# microSD-v2017-2.net
KiCad netlist of a schematic drawn in EAGLE
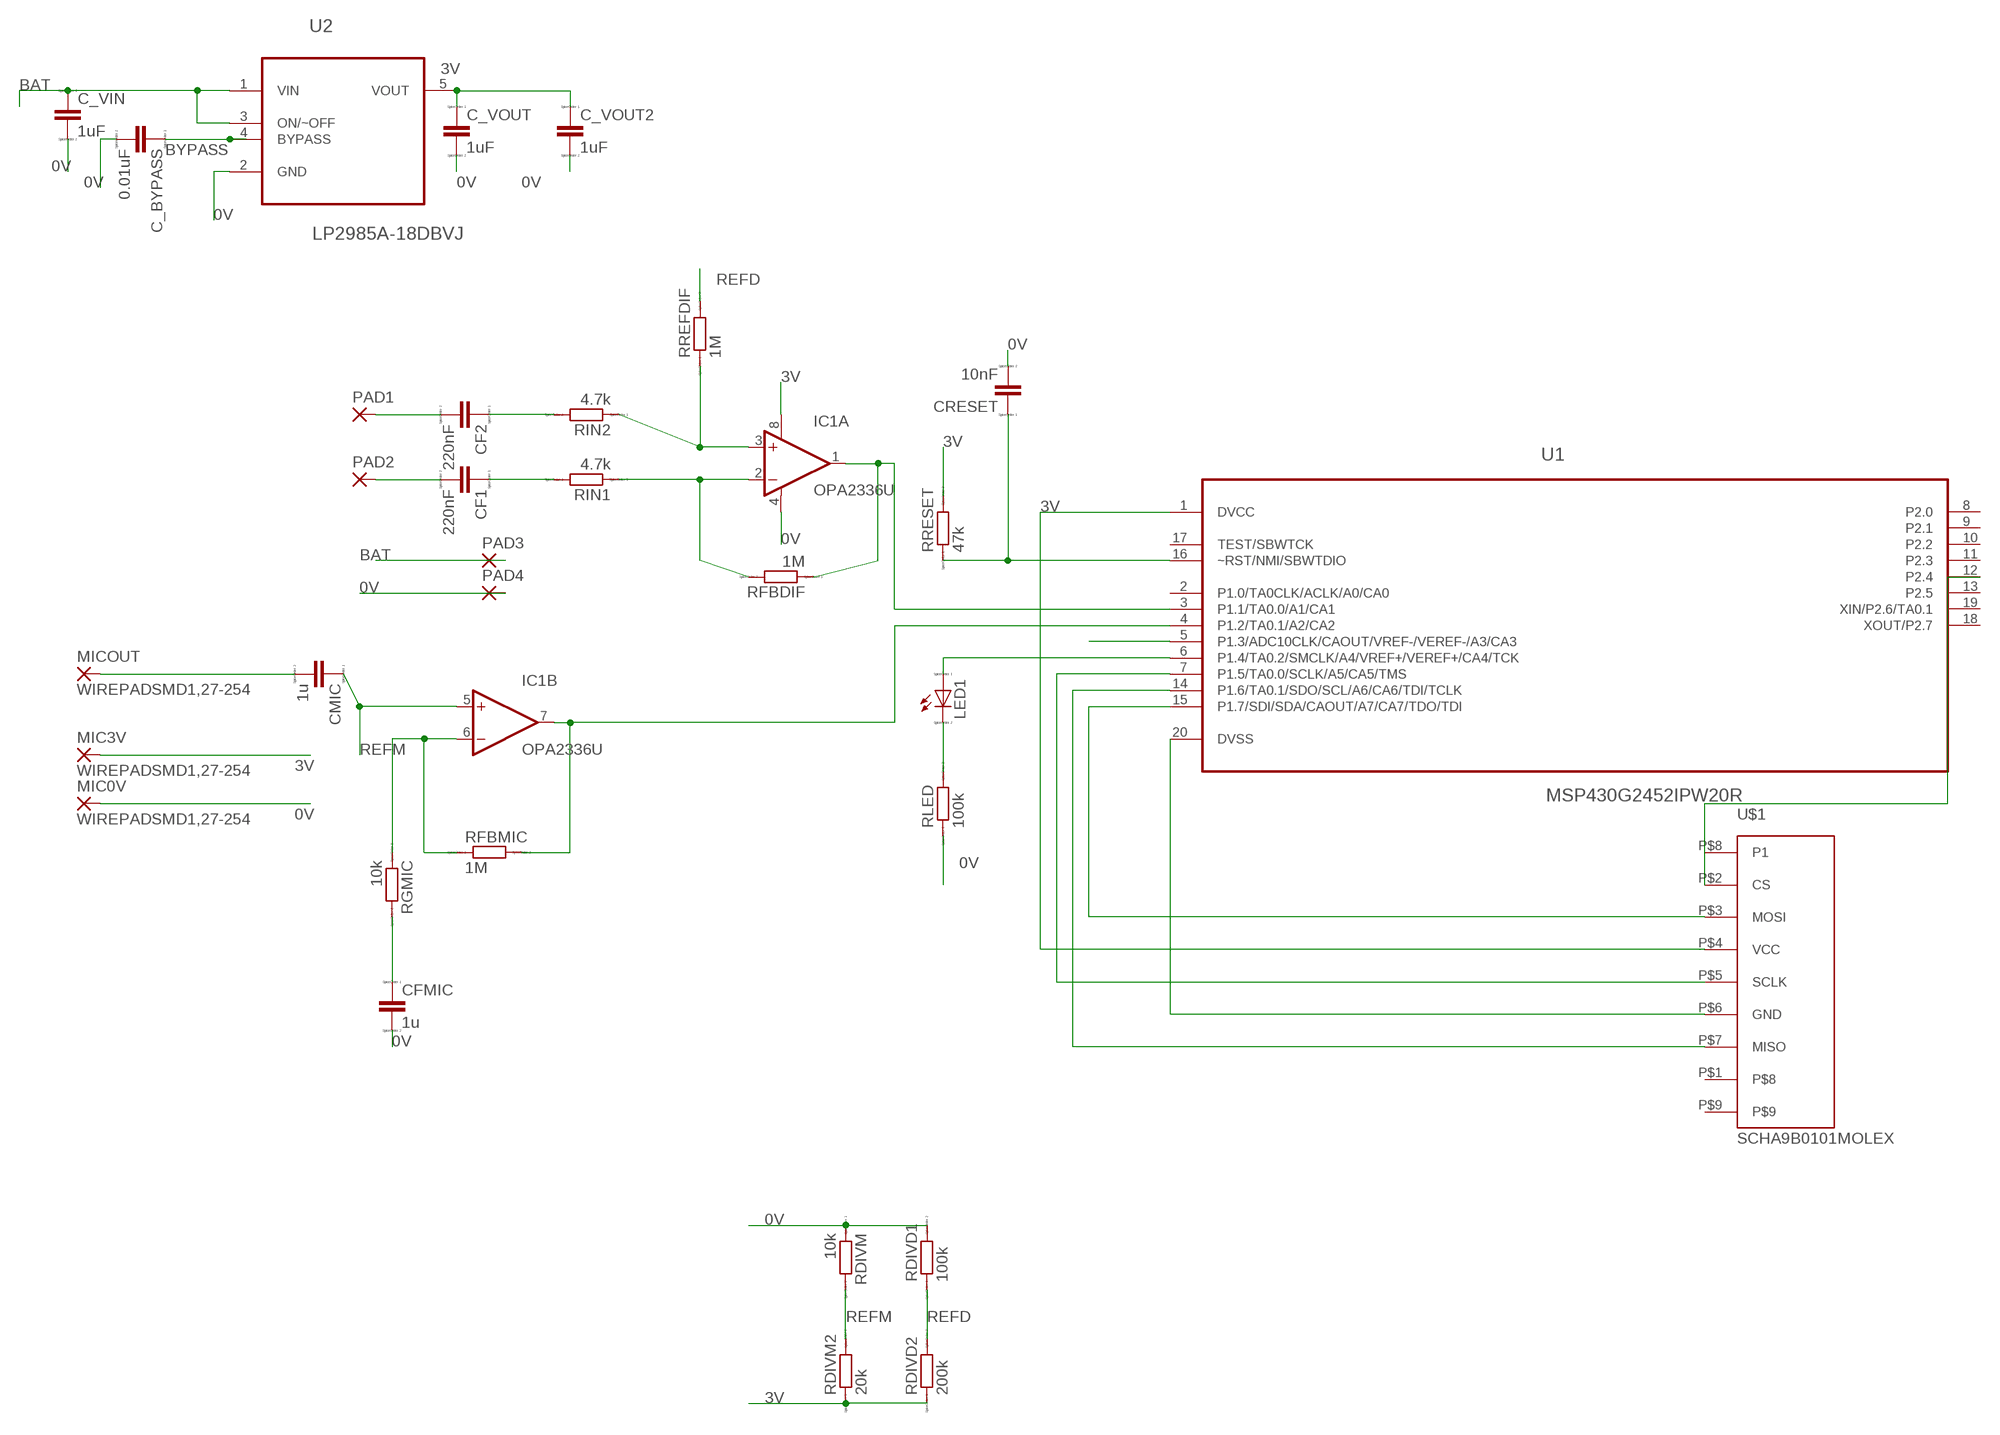
[diagram p0: schematic, sheet 1]

(export (version "E")
  (design (tool "Eeschema 10.0.6"))
  (components
    (comp (ref "CF1")
      (value "220nF")
      (footprint "eagle-import:C0805")
      (libsource (lib "eagle-import") (part "C"))
    )
    (comp (ref "CF2")
      (value "220nF")
      (footprint "eagle-import:C0805")
      (libsource (lib "eagle-import") (part "C"))
    )
    (comp (ref "CFMIC")
      (value "1u")
      (footprint "eagle-import:C0805")
      (libsource (lib "eagle-import") (part "C"))
    )
    (comp (ref "CMIC")
      (value "1u")
      (footprint "eagle-import:C0805")
      (libsource (lib "eagle-import") (part "C"))
    )
    (comp (ref "CRESET")
      (value "10nF")
      (footprint "eagle-import:C0805")
      (libsource (lib "eagle-import") (part "C"))
    )
    (comp (ref "C_BYPASS")
      (value "0.01uF")
      (footprint "eagle-import:C0805")
      (libsource (lib "eagle-import") (part "C"))
    )
    (comp (ref "C_VIN")
      (value "1uF")
      (footprint "eagle-import:C0805")
      (libsource (lib "eagle-import") (part "C"))
    )
    (comp (ref "C_VOUT")
      (value "1uF")
      (footprint "eagle-import:C0805")
      (libsource (lib "eagle-import") (part "C"))
    )
    (comp (ref "C_VOUT2")
      (value "1uF")
      (footprint "eagle-import:C0805")
      (libsource (lib "eagle-import") (part "C"))
    )
    (comp (ref "IC1")
      (value "OPA2336U")
      (footprint "eagle-import:SO08")
      (fields (field (name "MPN") "OPA2336UA"))
      (libsource (lib "eagle-import") (part "OPA2336U"))
    )
    (comp (ref "LED1")
      (value "LED_ESML0603")
      (footprint "eagle-import:LED_SML0603")
      (libsource (lib "eagle-import") (part "LED_ESML0603"))
    )
    (comp (ref "MIC0V")
      (value "WIREPADSMD1,27-254")
      (footprint "eagle-import:SMD1,27-2,54")
      (libsource (lib "eagle-import") (part "WIREPADSMD1,27-254"))
    )
    (comp (ref "MIC3V")
      (value "WIREPADSMD1,27-254")
      (footprint "eagle-import:SMD1,27-2,54")
      (libsource (lib "eagle-import") (part "WIREPADSMD1,27-254"))
    )
    (comp (ref "MICOUT")
      (value "WIREPADSMD1,27-254")
      (footprint "eagle-import:SMD1,27-2,54")
      (libsource (lib "eagle-import") (part "WIREPADSMD1,27-254"))
    )
    (comp (ref "PAD1")
      (value "SMD2")
      (footprint "eagle-import:SMD1,27-2,54")
      (libsource (lib "eagle-import") (part "SMD2"))
    )
    (comp (ref "PAD2")
      (value "SMD2")
      (footprint "eagle-import:SMD1,27-2,54")
      (libsource (lib "eagle-import") (part "SMD2"))
    )
    (comp (ref "PAD3")
      (value "SMD2")
      (footprint "eagle-import:SMD1,27-2,54")
      (libsource (lib "eagle-import") (part "SMD2"))
    )
    (comp (ref "PAD4")
      (value "SMD2")
      (footprint "eagle-import:SMD1,27-2,54")
      (libsource (lib "eagle-import") (part "SMD2"))
    )
    (comp (ref "RDIVD1")
      (value "100k")
      (footprint "eagle-import:R0805")
      (libsource (lib "eagle-import") (part "R"))
    )
    (comp (ref "RDIVD2")
      (value "200k")
      (footprint "eagle-import:R0805")
      (libsource (lib "eagle-import") (part "R"))
    )
    (comp (ref "RDIVM")
      (value "10k")
      (footprint "eagle-import:R0805")
      (libsource (lib "eagle-import") (part "R"))
    )
    (comp (ref "RDIVM2")
      (value "20k")
      (footprint "eagle-import:R0805")
      (libsource (lib "eagle-import") (part "R"))
    )
    (comp (ref "RFBDIF")
      (value "1M")
      (footprint "eagle-import:R0805")
      (libsource (lib "eagle-import") (part "R"))
    )
    (comp (ref "RFBMIC")
      (value "1M")
      (footprint "eagle-import:R0805")
      (libsource (lib "eagle-import") (part "R"))
    )
    (comp (ref "RGMIC")
      (value "10k")
      (footprint "eagle-import:R0805")
      (libsource (lib "eagle-import") (part "R"))
    )
    (comp (ref "RIN1")
      (value "4.7k")
      (footprint "eagle-import:R0805")
      (libsource (lib "eagle-import") (part "R"))
    )
    (comp (ref "RIN2")
      (value "4.7k")
      (footprint "eagle-import:R0805")
      (libsource (lib "eagle-import") (part "R"))
    )
    (comp (ref "RLED")
      (value "100k")
      (footprint "eagle-import:R0603")
      (libsource (lib "eagle-import") (part "RR0603"))
    )
    (comp (ref "RREFDIF")
      (value "1M")
      (footprint "eagle-import:R0805")
      (libsource (lib "eagle-import") (part "R"))
    )
    (comp (ref "RRESET")
      (value "47k")
      (footprint "eagle-import:R0805")
      (libsource (lib "eagle-import") (part "R"))
    )
    (comp (ref "U$1")
      (value "SCHA9B0101MOLEX")
      (footprint "eagle-import:SMD-MOLEX")
      (libsource (lib "eagle-import") (part "SCHA9B0101MOLEX"))
    )
    (comp (ref "U1")
      (value "MSP430G2452IPW20R")
      (footprint "eagle-import:SOP65P640X120-20N")
      (libsource (lib "eagle-import") (part "MSP430G2452IPW20R"))
    )
    (comp (ref "U2")
      (value "LP2985A-18DBVJ")
      (footprint "eagle-import:SOT95P280X145-5N")
      (libsource (lib "eagle-import") (part "LP2985A-18DBVJ"))
    )
  )
  (nets
    (net (code "1") (name "/0V") (class "Default")
      (node (ref "CFMIC") (pin "2") (pinfunction "2_2") (pintype "passive"))
      (node (ref "CRESET") (pin "2") (pinfunction "2_2") (pintype "passive"))
      (node (ref "C_BYPASS") (pin "2") (pinfunction "2_2") (pintype "passive"))
      (node (ref "C_VIN") (pin "2") (pinfunction "2_2") (pintype "passive"))
      (node (ref "C_VOUT") (pin "2") (pinfunction "2_2") (pintype "passive"))
      (node (ref "C_VOUT2") (pin "2") (pinfunction "2_2") (pintype "passive"))
      (node (ref "IC1") (pin "4") (pinfunction "V-_4") (pintype "power_in"))
      (node (ref "MIC0V") (pin "1") (pinfunction "P_1") (pintype "passive"))
      (node (ref "PAD4") (pin "1") (pinfunction "P_1") (pintype "passive"))
      (node (ref "RDIVD1") (pin "2") (pinfunction "2_2") (pintype "passive"))
      (node (ref "RDIVM") (pin "1") (pinfunction "1_1") (pintype "passive"))
      (node (ref "RLED") (pin "1") (pinfunction "1_1") (pintype "passive"))
      (node (ref "U$1") (pin "P$6") (pinfunction "GND_P$6") (pintype "bidirectional"))
      (node (ref "U1") (pin "20") (pinfunction "DVSS_20") (pintype "passive"))
      (node (ref "U2") (pin "2") (pinfunction "GND_2") (pintype "passive"))
    )
    (net (code "2") (name "/3V") (class "Default")
      (node (ref "C_VOUT") (pin "1") (pinfunction "1_1") (pintype "passive"))
      (node (ref "C_VOUT2") (pin "1") (pinfunction "1_1") (pintype "passive"))
      (node (ref "IC1") (pin "8") (pinfunction "V+_8") (pintype "power_in"))
      (node (ref "MIC3V") (pin "1") (pinfunction "P_1") (pintype "passive"))
      (node (ref "RDIVD2") (pin "1") (pinfunction "1_1") (pintype "passive"))
      (node (ref "RDIVM2") (pin "1") (pinfunction "1_1") (pintype "passive"))
      (node (ref "RRESET") (pin "2") (pinfunction "2_2") (pintype "passive"))
      (node (ref "U$1") (pin "P$4") (pinfunction "VCC_P$4") (pintype "bidirectional"))
      (node (ref "U1") (pin "1") (pinfunction "DVCC_1") (pintype "power_in"))
      (node (ref "U2") (pin "5") (pinfunction "VOUT_5") (pintype "output"))
    )
    (net (code "3") (name "/BAT") (class "Default")
      (node (ref "C_VIN") (pin "1") (pinfunction "1_1") (pintype "passive"))
      (node (ref "PAD3") (pin "1") (pinfunction "P_1") (pintype "passive"))
      (node (ref "U2") (pin "1") (pinfunction "VIN_1") (pintype "input"))
      (node (ref "U2") (pin "3") (pinfunction "ON/~{OFF}_3") (pintype "input"))
    )
    (net (code "4") (name "/BYPASS") (class "Default")
      (node (ref "C_BYPASS") (pin "1") (pinfunction "1_1") (pintype "passive"))
      (node (ref "U2") (pin "4") (pinfunction "BYPASS_4") (pintype "input"))
    )
    (net (code "5") (name "/REFD") (class "Default")
      (node (ref "RDIVD1") (pin "1") (pinfunction "1_1") (pintype "passive"))
      (node (ref "RDIVD2") (pin "2") (pinfunction "2_2") (pintype "passive"))
      (node (ref "RREFDIF") (pin "2") (pinfunction "2_2") (pintype "passive"))
    )
    (net (code "6") (name "/REFM") (class "Default")
      (node (ref "CMIC") (pin "1") (pinfunction "1_1") (pintype "passive"))
      (node (ref "IC1") (pin "5") (pinfunction "+IN_5") (pintype "input"))
      (node (ref "RDIVM") (pin "2") (pinfunction "2_2") (pintype "passive"))
      (node (ref "RDIVM2") (pin "2") (pinfunction "2_2") (pintype "passive"))
    )
    (net (code "7") (name "Net-(CF1-Pad1)") (class "Default")
      (node (ref "CF1") (pin "1") (pinfunction "1_1") (pintype "passive"))
      (node (ref "RIN1") (pin "2") (pinfunction "2_2") (pintype "passive"))
    )
    (net (code "8") (name "Net-(CF2-Pad1)") (class "Default")
      (node (ref "CF2") (pin "1") (pinfunction "1_1") (pintype "passive"))
      (node (ref "RIN2") (pin "2") (pinfunction "2_2") (pintype "passive"))
    )
    (net (code "9") (name "Net-(CFMIC-Pad1)") (class "Default")
      (node (ref "CFMIC") (pin "1") (pinfunction "1_1") (pintype "passive"))
      (node (ref "RGMIC") (pin "2") (pinfunction "2_2") (pintype "passive"))
    )
    (net (code "10") (name "Net-(IC1A-+IN)") (class "Default")
      (node (ref "IC1") (pin "3") (pinfunction "+IN_3") (pintype "input"))
      (node (ref "RIN2") (pin "1") (pinfunction "1_1") (pintype "passive"))
      (node (ref "RREFDIF") (pin "1") (pinfunction "1_1") (pintype "passive"))
    )
    (net (code "11") (name "Net-(IC1A--IN)") (class "Default")
      (node (ref "IC1") (pin "2") (pinfunction "-IN_2") (pintype "input"))
      (node (ref "RFBDIF") (pin "2") (pinfunction "2_2") (pintype "passive"))
      (node (ref "RIN1") (pin "1") (pinfunction "1_1") (pintype "passive"))
    )
    (net (code "12") (name "Net-(IC1A-OUT)") (class "Default")
      (node (ref "IC1") (pin "1") (pinfunction "OUT_1") (pintype "output"))
      (node (ref "RFBDIF") (pin "1") (pinfunction "1_1") (pintype "passive"))
      (node (ref "U1") (pin "3") (pinfunction "P1.1/TA0.0/A1/CA1_3") (pintype "bidirectional"))
    )
    (net (code "13") (name "Net-(IC1B--IN)") (class "Default")
      (node (ref "IC1") (pin "6") (pinfunction "-IN_6") (pintype "input"))
      (node (ref "RFBMIC") (pin "1") (pinfunction "1_1") (pintype "passive"))
      (node (ref "RGMIC") (pin "1") (pinfunction "1_1") (pintype "passive"))
    )
    (net (code "14") (name "Net-(IC1B-OUT)") (class "Default")
      (node (ref "IC1") (pin "7") (pinfunction "OUT_7") (pintype "output"))
      (node (ref "RFBMIC") (pin "2") (pinfunction "2_2") (pintype "passive"))
      (node (ref "U1") (pin "4") (pinfunction "P1.2/TA0.1/A2/CA2_4") (pintype "bidirectional"))
    )
    (net (code "15") (name "Net-(LED1-PadC)") (class "Default")
      (node (ref "LED1") (pin "C") (pinfunction "C_C") (pintype "passive"))
      (node (ref "RLED") (pin "2") (pinfunction "2_2") (pintype "passive"))
    )
    (net (code "16") (name "Net-(MICOUT-P)") (class "Default")
      (node (ref "CMIC") (pin "2") (pinfunction "2_2") (pintype "passive"))
      (node (ref "MICOUT") (pin "1") (pinfunction "P_1") (pintype "passive"))
    )
    (net (code "17") (name "Net-(PAD1-P)") (class "Default")
      (node (ref "CF2") (pin "2") (pinfunction "2_2") (pintype "passive"))
      (node (ref "PAD1") (pin "1") (pinfunction "P_1") (pintype "passive"))
    )
    (net (code "18") (name "Net-(PAD2-P)") (class "Default")
      (node (ref "CF1") (pin "2") (pinfunction "2_2") (pintype "passive"))
      (node (ref "PAD2") (pin "1") (pinfunction "P_1") (pintype "passive"))
    )
    (net (code "19") (name "Net-(U$1-CS)") (class "Default")
      (node (ref "U$1") (pin "P$2") (pinfunction "CS_P$2") (pintype "bidirectional"))
      (node (ref "U1") (pin "12") (pinfunction "P2.4_12") (pintype "bidirectional"))
    )
    (net (code "20") (name "Net-(U$1-MISO)") (class "Default")
      (node (ref "U$1") (pin "P$7") (pinfunction "MISO_P$7") (pintype "bidirectional"))
      (node (ref "U1") (pin "14") (pinfunction "P1.6/TA0.1/SDO/SCL/A6/CA6/TDI/TCLK_14") (pintype "bidirectional"))
    )
    (net (code "21") (name "Net-(U$1-MOSI)") (class "Default")
      (node (ref "U$1") (pin "P$3") (pinfunction "MOSI_P$3") (pintype "bidirectional"))
      (node (ref "U1") (pin "15") (pinfunction "P1.7/SDI/SDA/CAOUT/A7/CA7/TDO/TDI_15") (pintype "bidirectional"))
    )
    (net (code "22") (name "Net-(U$1-SCLK)") (class "Default")
      (node (ref "U$1") (pin "P$5") (pinfunction "SCLK_P$5") (pintype "bidirectional"))
      (node (ref "U1") (pin "7") (pinfunction "P1.5/TA0.0/SCLK/A5/CA5/TMS_7") (pintype "bidirectional"))
    )
    (net (code "23") (name "Net-(U1-P1.4{slash}TA0.2{slash}SMCLK{slash}A4{slash}VREF+{slash}VEREF+{slash}CA4{slash}TCK)") (class "Default")
      (node (ref "LED1") (pin "A") (pinfunction "A_A") (pintype "passive"))
      (node (ref "U1") (pin "6") (pinfunction "P1.4/TA0.2/SMCLK/A4/VREF+/VEREF+/CA4/TCK_6") (pintype "bidirectional"))
    )
    (net (code "24") (name "Net-(U1-~{RST{slash}NMI{slash}SBWTDIO})") (class "Default")
      (node (ref "CRESET") (pin "1") (pinfunction "1_1") (pintype "passive"))
      (node (ref "RRESET") (pin "1") (pinfunction "1_1") (pintype "passive"))
      (node (ref "U1") (pin "16") (pinfunction "~{RST/NMI/SBWTDIO}_16") (pintype "input"))
    )
    (net (code "25") (name "unconnected-(U$1-P$8-PadP$1)") (class "Default")
      (node (ref "U$1") (pin "P$1") (pinfunction "P$8_P$1") (pintype "bidirectional"))
    )
    (net (code "26") (name "unconnected-(U$1-P1-PadP$8)") (class "Default")
      (node (ref "U$1") (pin "P$8") (pinfunction "P1_P$8") (pintype "bidirectional"))
    )
    (net (code "27") (name "unconnected-(U$1-PadP$9)") (class "Default")
      (node (ref "U$1") (pin "P$9") (pinfunction "P$9_P$9") (pintype "bidirectional"))
    )
    (net (code "28") (name "unconnected-(U1-P1.0{slash}TA0CLK{slash}ACLK{slash}A0{slash}CA0-Pad2)") (class "Default")
      (node (ref "U1") (pin "2") (pinfunction "P1.0/TA0CLK/ACLK/A0/CA0_2") (pintype "bidirectional"))
    )
    (net (code "29") (name "unconnected-(U1-P1.3{slash}ADC10CLK{slash}CAOUT{slash}VREF-{slash}VEREF-{slash}A3{slash}CA3-Pad5)") (class "Default")
      (node (ref "U1") (pin "5") (pinfunction "P1.3/ADC10CLK/CAOUT/VREF-/VEREF-/A3/CA3_5") (pintype "bidirectional"))
    )
    (net (code "30") (name "unconnected-(U1-P2.0-Pad8)") (class "Default")
      (node (ref "U1") (pin "8") (pinfunction "P2.0_8") (pintype "bidirectional"))
    )
    (net (code "31") (name "unconnected-(U1-P2.1-Pad9)") (class "Default")
      (node (ref "U1") (pin "9") (pinfunction "P2.1_9") (pintype "bidirectional"))
    )
    (net (code "32") (name "unconnected-(U1-P2.2-Pad10)") (class "Default")
      (node (ref "U1") (pin "10") (pinfunction "P2.2_10") (pintype "bidirectional"))
    )
    (net (code "33") (name "unconnected-(U1-P2.3-Pad11)") (class "Default")
      (node (ref "U1") (pin "11") (pinfunction "P2.3_11") (pintype "bidirectional"))
    )
    (net (code "34") (name "unconnected-(U1-P2.5-Pad13)") (class "Default")
      (node (ref "U1") (pin "13") (pinfunction "P2.5_13") (pintype "bidirectional"))
    )
    (net (code "35") (name "unconnected-(U1-TEST{slash}SBWTCK-Pad17)") (class "Default")
      (node (ref "U1") (pin "17") (pinfunction "TEST/SBWTCK_17") (pintype "input"))
    )
    (net (code "36") (name "unconnected-(U1-XIN{slash}P2.6{slash}TA0.1-Pad19)") (class "Default")
      (node (ref "U1") (pin "19") (pinfunction "XIN/P2.6/TA0.1_19") (pintype "bidirectional"))
    )
    (net (code "37") (name "unconnected-(U1-XOUT{slash}P2.7-Pad18)") (class "Default")
      (node (ref "U1") (pin "18") (pinfunction "XOUT/P2.7_18") (pintype "bidirectional"))
    )
  )
)
